# dctodcisole.net
KiCad netlist of a schematic drawn in Altium Designer
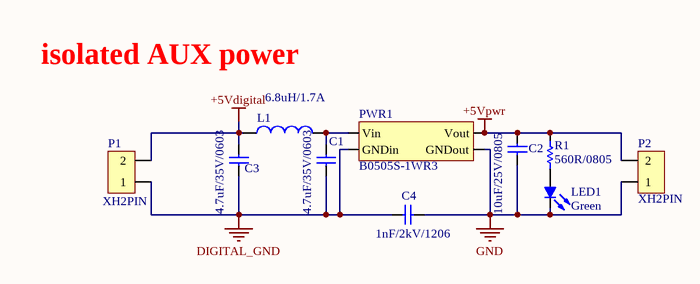
[diagram p0: dctodcisole.SchDoc]

(export (version "E")
  (design (tool "Eeschema 10.0.6"))
  (components
    (comp (ref "C1")
      (value "4.7uF/35V/0603")
      (footprint "cap 0603")
      (description "Capacitor")
      (libsource (lib "Schlib") (part "Capacitor"))
    )
    (comp (ref "C2")
      (value "10uF/25V/0805")
      (footprint "CAP 0805")
      (description "Capacitor")
      (libsource (lib "Schlib") (part "Capacitor"))
    )
    (comp (ref "C3")
      (value "4.7uF/35V/0603")
      (footprint "cap 0603")
      (description "Capacitor")
      (libsource (lib "Schlib") (part "Capacitor"))
    )
    (comp (ref "C4")
      (value "1nF/2kV/1206")
      (footprint "CAP 1206")
      (description "Capacitor")
      (libsource (lib "Schlib") (part "Capacitor"))
    )
    (comp (ref "L1")
      (value "6.8uH/1.7A")
      (footprint "1008(2520 metric)")
      (description "Inductor")
      (libsource (lib "PFC NCP1653A 1KW") (part "Inductor"))
    )
    (comp (ref "LED1")
      (value "LED 3mm/Green")
      (footprint "LED 3mm")
      (description "Typical LED")
      (fields (field (name "COLOR") "Green"))
      (libsource (lib "TL494 12V-20A-KARA") (part "LED"))
    )
    (comp (ref "P1")
      (value "XH2PIN")
      (footprint "pin-header 2*1")
      (description "RELAY")
      (fields (field (name "PUBLISHER") "Altium Limited"))
      (libsource (lib "Schlib") (part "Header 2H"))
    )
    (comp (ref "P2")
      (value "XH2PIN")
      (footprint "pin-header 2*1")
      (description "RELAY")
      (fields (field (name "PUBLISHER") "Altium Limited"))
      (libsource (lib "") (part "Header 2H_1"))
    )
    (comp (ref "PWR1")
      (value "B0505S-1WR3")
      (footprint "B0505S")
      (libsource (lib "Schlib") (part "B0505S-1WR3"))
    )
    (comp (ref "R1") (value "560R/0805") (footprint "RES 0805") (libsource (lib "Schlib") (part "Res")))
  )
  (nets
    (net (code "1") (name "+5Vdigital") (class "Default")
      (node (ref "C3") (pin "1") (pinfunction "+_1") (pintype "passive"))
      (node (ref "L1") (pin "1") (pinfunction "1_1") (pintype "passive"))
      (node (ref "P1") (pin "2") (pinfunction "2_2") (pintype "passive"))
    )
    (net (code "2") (name "+5Vpwr") (class "Default")
      (node (ref "C2") (pin "1") (pinfunction "+_1") (pintype "passive"))
      (node (ref "P2") (pin "2") (pinfunction "2_2") (pintype "passive"))
      (node (ref "PWR1") (pin "4") (pinfunction "Vout_4") (pintype "passive"))
      (node (ref "R1") (pin "2") (pinfunction "2_2") (pintype "passive"))
    )
    (net (code "3") (name "DIGITAL_GND") (class "Default")
      (node (ref "C1") (pin "2") (pinfunction "-_2") (pintype "passive"))
      (node (ref "C3") (pin "2") (pinfunction "-_2") (pintype "passive"))
      (node (ref "C4") (pin "1") (pinfunction "+_1") (pintype "passive"))
      (node (ref "P1") (pin "1") (pinfunction "1_1") (pintype "passive"))
      (node (ref "PWR1") (pin "1") (pinfunction "GNDin_1") (pintype "passive"))
    )
    (net (code "4") (name "GND") (class "Default")
      (node (ref "C2") (pin "2") (pinfunction "-_2") (pintype "passive"))
      (node (ref "C4") (pin "2") (pinfunction "-_2") (pintype "passive"))
      (node (ref "LED1") (pin "2") (pinfunction "K_2") (pintype "passive"))
      (node (ref "P2") (pin "1") (pinfunction "1_1") (pintype "passive"))
      (node (ref "PWR1") (pin "3") (pinfunction "GNDout_3") (pintype "passive"))
    )
    (net (code "5") (name "Net-(C1-+)") (class "Default")
      (node (ref "C1") (pin "1") (pinfunction "+_1") (pintype "passive"))
      (node (ref "L1") (pin "2") (pinfunction "2_2") (pintype "passive"))
      (node (ref "PWR1") (pin "2") (pinfunction "Vin_2") (pintype "passive"))
    )
    (net (code "6") (name "Net-(LED1-A)") (class "Default")
      (node (ref "LED1") (pin "1") (pinfunction "A_1") (pintype "passive"))
      (node (ref "R1") (pin "1") (pinfunction "1_1") (pintype "passive"))
    )
  )
)
